# SingleASIC.net
KiCad netlist of a schematic drawn in Altium Designer
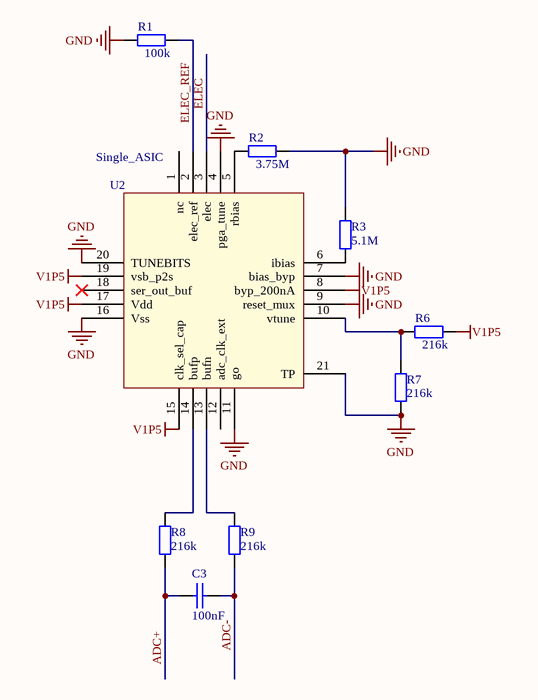
[diagram p0: SingleASIC.SchDoc]

(export (version "E")
  (design (tool "Eeschema 10.0.6"))
  (components
    (comp (ref "C3")
      (value "100nF")
      (footprint "0402L")
      (description "Capacitor")
      (fields (field (name "Comment") "NP0 50V"))
      (libsource (lib "nRF24LE1F16Q24") (part "Cap"))
    )
    (comp (ref "R1")
      (value "100k")
      (footprint "0402L")
      (description "Resistor")
      (fields (field (name "Comment") "Res2") (field (name "PUBLISHER") "Altium Limited"))
      (libsource (lib "Miscellaneous Devices") (part "Res2"))
    )
    (comp (ref "R2")
      (value "3.75M")
      (footprint "0402L")
      (description "Resistor")
      (fields (field (name "Comment") "Res2") (field (name "PUBLISHER") "Altium Limited"))
      (libsource (lib "Miscellaneous Devices") (part "Res2"))
    )
    (comp (ref "R3")
      (value "5.1M")
      (footprint "0402L")
      (description "Resistor")
      (fields (field (name "Comment") "Res2") (field (name "PUBLISHER") "Altium Limited"))
      (libsource (lib "") (part "Res2_1"))
    )
    (comp (ref "R6")
      (value "216k")
      (footprint "0402L")
      (description "Resistor")
      (fields (field (name "Comment") "Res2") (field (name "PUBLISHER") "Altium Limited"))
      (libsource (lib "Miscellaneous Devices") (part "Res2"))
    )
    (comp (ref "R7")
      (value "216k")
      (footprint "0402L")
      (description "Resistor")
      (fields (field (name "Comment") "Res2") (field (name "PUBLISHER") "Altium Limited"))
      (libsource (lib "") (part "Res2_1"))
    )
    (comp (ref "R8")
      (value "216k")
      (footprint "0402L")
      (description "Resistor")
      (fields (field (name "Comment") "Res2") (field (name "PUBLISHER") "Altium Limited"))
      (libsource (lib "") (part "Res2_1"))
    )
    (comp (ref "R9")
      (value "216k")
      (footprint "0402L")
      (description "Resistor")
      (fields (field (name "Comment") "Res2") (field (name "PUBLISHER") "Altium Limited"))
      (libsource (lib "") (part "Res2_1"))
    )
    (comp (ref "U2")
      (value "Single_ASIC")
      (footprint "Single_ASIC")
      (libsource (lib "custom") (part "Single_ASIC"))
    )
  )
  (nets
    (net (code "1") (name "/ADC+") (class "Default")
      (node (ref "C3") (pin "1") (pintype "passive"))
      (node (ref "R8") (pin "1") (pinfunction "1_1") (pintype "passive"))
    )
    (net (code "2") (name "/ADC-") (class "Default")
      (node (ref "C3") (pin "2") (pintype "passive"))
      (node (ref "R9") (pin "1") (pinfunction "1_1") (pintype "passive"))
    )
    (net (code "3") (name "/ELEC") (class "Default")
      (node (ref "U2") (pin "3") (pinfunction "elec_3") (pintype "passive"))
    )
    (net (code "4") (name "/ELEC_REF") (class "Default")
      (node (ref "R1") (pin "2") (pinfunction "2_2") (pintype "passive"))
      (node (ref "U2") (pin "2") (pinfunction "elec_ref_2") (pintype "passive"))
    )
    (net (code "5") (name "GND") (class "Default")
      (node (ref "R1") (pin "1") (pinfunction "1_1") (pintype "passive"))
      (node (ref "R2") (pin "2") (pinfunction "2_2") (pintype "passive"))
      (node (ref "R3") (pin "2") (pinfunction "2_2") (pintype "passive"))
      (node (ref "R7") (pin "1") (pinfunction "1_1") (pintype "passive"))
      (node (ref "U2") (pin "11") (pinfunction "go_11") (pintype "passive"))
      (node (ref "U2") (pin "16") (pinfunction "Vss_16") (pintype "passive"))
      (node (ref "U2") (pin "20") (pinfunction "TUNEBITS_20") (pintype "passive"))
      (node (ref "U2") (pin "21") (pinfunction "TP_21") (pintype "passive"))
      (node (ref "U2") (pin "4") (pinfunction "pga_tune_4") (pintype "passive"))
      (node (ref "U2") (pin "7") (pinfunction "bias_byp_7") (pintype "passive"))
      (node (ref "U2") (pin "9") (pinfunction "reset_mux_9") (pintype "passive"))
    )
    (net (code "6") (name "Net-(U2-bufn)") (class "Default")
      (node (ref "R9") (pin "2") (pinfunction "2_2") (pintype "passive"))
      (node (ref "U2") (pin "13") (pinfunction "bufn_13") (pintype "passive"))
    )
    (net (code "7") (name "Net-(U2-bufp)") (class "Default")
      (node (ref "R8") (pin "2") (pinfunction "2_2") (pintype "passive"))
      (node (ref "U2") (pin "14") (pinfunction "bufp_14") (pintype "passive"))
    )
    (net (code "8") (name "Net-(U2-ibias)") (class "Default")
      (node (ref "R3") (pin "1") (pinfunction "1_1") (pintype "passive"))
      (node (ref "U2") (pin "6") (pinfunction "ibias_6") (pintype "passive"))
    )
    (net (code "9") (name "Net-(U2-rbias)") (class "Default")
      (node (ref "R2") (pin "1") (pinfunction "1_1") (pintype "passive"))
      (node (ref "U2") (pin "5") (pinfunction "rbias_5") (pintype "passive"))
    )
    (net (code "10") (name "Net-(U2-vtune)") (class "Default")
      (node (ref "R6") (pin "1") (pinfunction "1_1") (pintype "passive"))
      (node (ref "R7") (pin "2") (pinfunction "2_2") (pintype "passive"))
      (node (ref "U2") (pin "10") (pinfunction "vtune_10") (pintype "passive"))
    )
    (net (code "11") (name "V1P5") (class "Default")
      (node (ref "R6") (pin "2") (pinfunction "2_2") (pintype "passive"))
      (node (ref "U2") (pin "15") (pinfunction "clk_sel_cap_15") (pintype "passive"))
      (node (ref "U2") (pin "17") (pinfunction "Vdd_17") (pintype "passive"))
      (node (ref "U2") (pin "19") (pinfunction "vsb_p2s_19") (pintype "passive"))
      (node (ref "U2") (pin "8") (pinfunction "byp_200nA_8") (pintype "passive"))
    )
    (net (code "12") (name "unconnected-(U2-adc_clk_ext-Pad12)") (class "Default")
      (node (ref "U2") (pin "12") (pinfunction "adc_clk_ext_12") (pintype "passive"))
    )
    (net (code "13") (name "unconnected-(U2-nc-Pad1)") (class "Default")
      (node (ref "U2") (pin "1") (pinfunction "nc_1") (pintype "passive"))
    )
    (net (code "14") (name "unconnected-(U2-ser_out_buf-Pad18)") (class "Default")
      (node (ref "U2") (pin "18") (pinfunction "ser_out_buf_18") (pintype "passive+no_connect"))
    )
  )
)
